# Power.net
KiCad netlist of a schematic drawn in Altium Designer
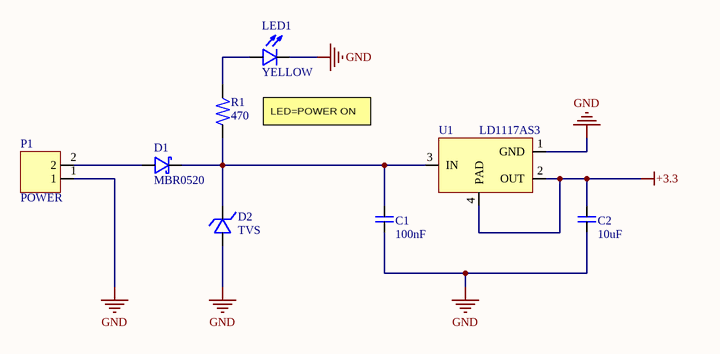
[diagram p0: Power.SchDoc]

(export (version "E")
  (design (tool "Eeschema 10.0.6"))
  (components
    (comp (ref "C1")
      (value "100nF")
      (footprint "SMT_CAP_0805(2012)_X5R-KYOCERA")
      (description "Multilayer Ceramic Capacitor 0805(2012) KYOCERA AVX 100nF 08055D104KAT2A 50VDC X5R")
      (libsource (lib "SMT_CAP_0805(2012)_X5R-KYOCERA") (part "SMT_CAP_0805(2012)_X5R-KYOCERA"))
    )
    (comp (ref "C2")
      (value "10uF")
      (footprint "SMT_CAP_1206(3216)_MURATA")
      (description "Ceramic Capacitor 1206(3216) MURATA 10uF 50VDC GCM31CD71H106KE36L X7T")
      (libsource (lib "SMT_CAP_1206(3216)_MURATA") (part "SMT_CAP_1206(3216)_MURATA"))
    )
    (comp (ref "D1")
      (value "MBR0520")
      (footprint "SMT_DIODE_SCH_SOD-123")
      (description "Schottky Diode If=500mA 20 V MBR0520L-TP SOD-123-2 by MCC")
      (libsource (lib "SMT_DIODE_SCH_SOD-123") (part "SMT_DIODE_SCH_SOD-123"))
    )
    (comp (ref "D2")
      (value "TVS")
      (footprint "SMT_DIODE_TVS_SMB")
      (description "Diode TVS Littelfuse 600W SZP6SMB6.8AT3G")
      (libsource (lib "SMT_DIODE_TVS_SMB") (part "SMT_DIODE_TVS_SMB"))
    )
    (comp (ref "LED1")
      (value "YELLOW")
      (footprint "SMT_LED_0805(2012)_WURTH")
      (description "LED 0805(2012) 20mA 2V 150080YS75000 by Wurth Elektronik")
      (libsource (lib "SMT_LED_0805(2012)_WURTH") (part "SMT_LED_0805(2012)_WURTH"))
    )
    (comp (ref "P1")
      (value "POWER")
      (footprint "THT_CON_WAFER_2P_LHE_C3004-WV02")
      (description "Connector Wafer LHE 2-Pin Pitch-3.00mm 250V/5A C3004-WV02")
      (libsource (lib "THT_CON_WAFER_2P_LHE_C3004-WV02") (part "THT_CON_WAFER_2P_LHE_C3004-WV02"))
    )
    (comp (ref "R1")
      (value "470")
      (footprint "SMT_RES_0805(2012)")
      (description "0805(2012) Resistor 1/4-1/8W 150V 2A")
      (libsource (lib "SMT_RES_0805(2012)") (part "SMT_RES_0805(2012)"))
    )
    (comp (ref "U1")
      (value "LD1117AS3")
      (footprint "SMT_VR_LD1117AS3")
      (description "Voltage Regulator ST LD1117AS33TR 1A 3.3V 10Vmax")
      (libsource (lib "SMT_VR_LD1117AS3") (part "SMT_VR_LD1117AS3"))
    )
  )
  (nets
    (net (code "1") (name "+3.3") (class "Default")
      (node (ref "C2") (pin "2") (pinfunction "2_2") (pintype "passive"))
      (node (ref "U1") (pin "2") (pinfunction "OUT_2") (pintype "passive"))
      (node (ref "U1") (pin "4") (pinfunction "PAD_4") (pintype "passive"))
    )
    (net (code "2") (name "GND") (class "Default")
      (node (ref "C1") (pin "1") (pinfunction "1_1") (pintype "passive"))
      (node (ref "C2") (pin "1") (pinfunction "1_1") (pintype "passive"))
      (node (ref "D2") (pin "1") (pinfunction "1_1") (pintype "passive"))
      (node (ref "LED1") (pin "1") (pinfunction "1_1") (pintype "passive"))
      (node (ref "P1") (pin "1") (pinfunction "1_1") (pintype "passive"))
      (node (ref "U1") (pin "1") (pinfunction "GND_1") (pintype "passive"))
    )
    (net (code "3") (name "Net-(D1-Pad1)") (class "Default")
      (node (ref "D1") (pin "1") (pinfunction "1_1") (pintype "passive"))
      (node (ref "P1") (pin "2") (pinfunction "2_2") (pintype "passive"))
    )
    (net (code "4") (name "Net-(LED1-Pad2)") (class "Default")
      (node (ref "LED1") (pin "2") (pinfunction "2_2") (pintype "passive"))
      (node (ref "R1") (pin "2") (pinfunction "2_2") (pintype "passive"))
    )
    (net (code "5") (name "Net-(U1-IN)") (class "Default")
      (node (ref "C1") (pin "2") (pinfunction "2_2") (pintype "passive"))
      (node (ref "D1") (pin "2") (pinfunction "2_2") (pintype "passive"))
      (node (ref "D2") (pin "2") (pinfunction "2_2") (pintype "passive"))
      (node (ref "R1") (pin "1") (pinfunction "1_1") (pintype "passive"))
      (node (ref "U1") (pin "3") (pinfunction "IN_3") (pintype "passive"))
    )
  )
)
